# Sensor_Controller.net
KiCad netlist of a schematic drawn in Altium Designer
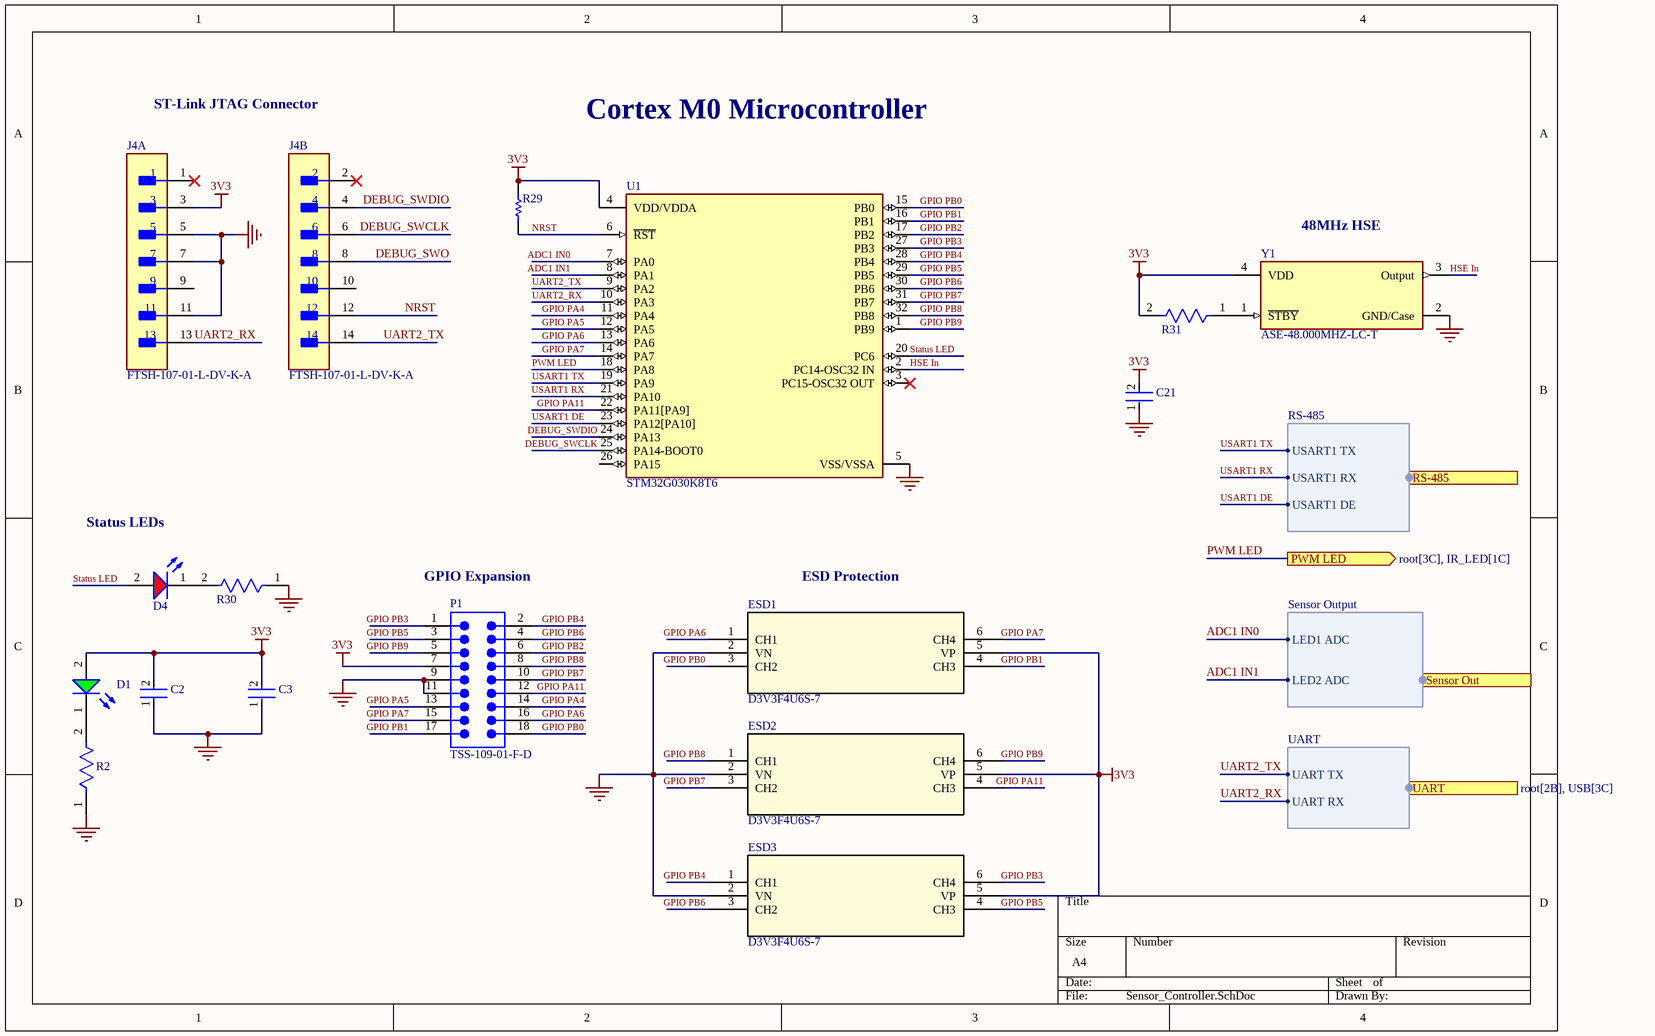
[diagram p0: Sensor_Controller.SchDoc]

(export (version "E")
  (design (tool "Eeschema 10.0.6"))
  (components
    (comp (ref "C2")
      (value "GRM188R6YA475KE15D")
      (footprint "FP-GRM188-0_2-IPC_C")
      (description "Chip Multilayer Ceramic Capacitors for General Purpose, 0603, 4.7uF, X5R, 15%, 10%, 35V")
      (fields (field (name "VOLTAGE") "35V") (field (name "TOLERANCE") "10%"))
      (libsource (lib "Altium Content Vault") (part "11868f565c42a9108669ba33697ecf6"))
    )
    (comp (ref "C3")
      (value "GRM155R71C104KA88D")
      (footprint "FP-GRM15-MFG")
      (description "CAP CER 0.1UF 16V X7R 0402")
      (fields
        (field (name "TOLERANCE") "10%")
        (field (name "OCTOPART") "https://octopart.com/grm155r71c104ka88d-murata-196880")
      )
      (libsource (lib "Altium Content Vault") (part "236180d848d6139a670b325ea6854c9"))
    )
    (comp (ref "C21")
      (value "GRM155R71C104KA88D")
      (footprint "FP-GRM15-MFG")
      (description "CAP CER 0.1UF 16V X7R 0402")
      (fields
        (field (name "TOLERANCE") "10%")
        (field (name "OCTOPART") "https://octopart.com/grm155r71c104ka88d-murata-196880")
      )
      (libsource (lib "Altium Content Vault") (part "236180d848d6139a670b325ea6854c9"))
    )
    (comp (ref "D1")
      (value "150060VS75000")
      (footprint "WL-SMCW_0603_150060xx75000")
      (description "WURTH ELEKTRONIK - 150060VS75000 - LED, Green, SMD, 0603, 30 mA, 2 V, 570 nm")
      (libsource (lib "Altium Content Vault") (part "LED_Green_2A-1K"))
    )
    (comp (ref "D4")
      (value "150060SS75000")
      (footprint "WL-SMCW_0603_150060xx75000")
      (description "Led, Red, 630 Nm, 1.9 V, 30 Ma, 60 Mcd Rohs Compliant: Yes")
      (libsource (lib "Altium Content Vault") (part "LED_Red_2A-1K"))
    )
    (comp (ref "ESD1")
      (value "D3V3F4U6S-7")
      (footprint "SOT-363_DIO")
      (description "No Description Available")
      (fields (field (name "COPYRIGHT") "Copyright (C) 2026 Ultra Librarian. All rights reserved."))
      (libsource (lib "D3V3F4U6S-7") (part "D3V3F4U6S-7"))
    )
    (comp (ref "ESD2")
      (value "D3V3F4U6S-7")
      (footprint "SOT-363_DIO")
      (description "No Description Available")
      (fields (field (name "COPYRIGHT") "Copyright (C) 2026 Ultra Librarian. All rights reserved."))
      (libsource (lib "D3V3F4U6S-7") (part "D3V3F4U6S-7"))
    )
    (comp (ref "ESD3")
      (value "D3V3F4U6S-7")
      (footprint "SOT-363_DIO")
      (description "No Description Available")
      (fields (field (name "COPYRIGHT") "Copyright (C) 2026 Ultra Librarian. All rights reserved."))
      (libsource (lib "D3V3F4U6S-7") (part "D3V3F4U6S-7"))
    )
    (comp (ref "J4")
      (value "FTSH-107-01-L-DV-K-A")
      (footprint "FP-FTSH-107-01-L-DV-K-A-MFG")
      (description "CONN HEADER SMD 14POS 1.27MM")
      (libsource (lib "Altium Content Vault") (part "45cc164b9edde9e1ad516d884ad4e1e"))
    )
    (comp (ref "P1")
      (value "TSS-109-01-F-D")
      (footprint "SMTC-TSS-109-01-X-D")
      (fields (field (name "MANUFACTURER") "Samtec"))
      (libsource (lib "Altium Content Vault") (part "SMTC-TSS-109-01-X-D"))
    )
    (comp (ref "R2")
      (value "RC0603FR-0710KL")
      (footprint "FP-RC0603-0_55-IPC_C")
      (description "RES 10K OHM 1% 1/10W 0603")
      (fields (field (name "TOLERANCE") "1%"))
      (libsource (lib "Altium Content Vault") (part "1029c3af85768c4190bb7ad29bc67b5"))
    )
    (comp (ref "R29")
      (value "TNPW040210K0DEED")
      (footprint "RESC1005X40X20NL05T10")
      (fields (field (name "MANUFACTURER") "Vishay BCcomponents"))
      (libsource (lib "Altium Content Vault") (part "RES"))
    )
    (comp (ref "R30")
      (value "RC0603FR-0710KL")
      (footprint "FP-RC0603-0_55-IPC_C")
      (description "RES 10K OHM 1% 1/10W 0603")
      (fields (field (name "TOLERANCE") "1%"))
      (libsource (lib "Altium Content Vault") (part "1029c3af85768c4190bb7ad29bc67b5"))
    )
    (comp (ref "R31")
      (value "RC0603FR-0710KL")
      (footprint "FP-RC0603-0_55-IPC_C")
      (description "RES 10K OHM 1% 1/10W 0603")
      (fields (field (name "TOLERANCE") "1%"))
      (libsource (lib "Altium Content Vault") (part "1029c3af85768c4190bb7ad29bc67b5"))
    )
    (comp (ref "U1")
      (value "STM32G030K8T6")
      (footprint "FP-LQFP32-5V-IPC_A")
      (description "IC MCU 32BIT 64KB FLASH 32LQFP")
      (libsource (lib "Altium Content Vault") (part "fea91388a178aa646681c81fcef9c35"))
    )
    (comp (ref "Y1")
      (value "ASE-48.000MHZ-LC-T")
      (footprint "FP-ASE-MFG")
      (description "XTAL Oscillator 48MHz ±50ppm CMOS 3.3V 4-SMD 3.2mm x 2.5mm")
      (libsource (lib "Altium Content Vault") (part "61a724e6190563596ac712fef61ad37"))
    )
  )
  (nets
    (net (code "5") (name "/ADC1 IN0") (class "Default")
      (node (ref "U1") (pin "7") (pinfunction "PA0_7") (pintype "bidirectional"))
    )
    (net (code "6") (name "/ADC1 IN1") (class "Default")
      (node (ref "U1") (pin "8") (pinfunction "PA1_8") (pintype "bidirectional"))
    )
    (net (code "7") (name "/DEBUG_SWCLK") (class "Default")
      (node (ref "J4") (pin "6") (pinfunction "6_6") (pintype "passive"))
      (node (ref "U1") (pin "25") (pinfunction "PA14-BOOT0_25") (pintype "bidirectional"))
    )
    (net (code "8") (name "/DEBUG_SWDIO") (class "Default")
      (node (ref "J4") (pin "4") (pinfunction "4_4") (pintype "passive"))
      (node (ref "U1") (pin "24") (pinfunction "PA13_24") (pintype "bidirectional"))
    )
    (net (code "9") (name "/DEBUG_SWO") (class "Default")
      (node (ref "J4") (pin "8") (pinfunction "8_8") (pintype "passive"))
    )
    (net (code "10") (name "/GPIO PA4") (class "Default")
      (node (ref "P1") (pin "14") (pinfunction "14_14") (pintype "passive"))
      (node (ref "U1") (pin "11") (pinfunction "PA4_11") (pintype "bidirectional"))
    )
    (net (code "11") (name "/GPIO PA5") (class "Default")
      (node (ref "P1") (pin "13") (pinfunction "13_13") (pintype "passive"))
      (node (ref "U1") (pin "12") (pinfunction "PA5_12") (pintype "bidirectional"))
    )
    (net (code "12") (name "/GPIO PA6") (class "Default")
      (node (ref "ESD1") (pin "1") (pinfunction "CH1_1") (pintype "passive"))
      (node (ref "P1") (pin "16") (pinfunction "16_16") (pintype "passive"))
      (node (ref "U1") (pin "13") (pinfunction "PA6_13") (pintype "bidirectional"))
    )
    (net (code "13") (name "/GPIO PA7") (class "Default")
      (node (ref "ESD1") (pin "6") (pinfunction "CH4_6") (pintype "passive"))
      (node (ref "P1") (pin "15") (pinfunction "15_15") (pintype "passive"))
      (node (ref "U1") (pin "14") (pinfunction "PA7_14") (pintype "bidirectional"))
    )
    (net (code "14") (name "/GPIO PA11") (class "Default")
      (node (ref "ESD2") (pin "4") (pinfunction "CH3_4") (pintype "passive"))
      (node (ref "P1") (pin "12") (pinfunction "12_12") (pintype "passive"))
      (node (ref "U1") (pin "22") (pinfunction "PA11[PA9]_22") (pintype "bidirectional"))
    )
    (net (code "15") (name "/GPIO PB0") (class "Default")
      (node (ref "ESD1") (pin "3") (pinfunction "CH2_3") (pintype "passive"))
      (node (ref "P1") (pin "18") (pinfunction "18_18") (pintype "passive"))
      (node (ref "U1") (pin "15") (pinfunction "PB0_15") (pintype "bidirectional"))
    )
    (net (code "16") (name "/GPIO PB1") (class "Default")
      (node (ref "ESD1") (pin "4") (pinfunction "CH3_4") (pintype "passive"))
      (node (ref "P1") (pin "17") (pinfunction "17_17") (pintype "passive"))
      (node (ref "U1") (pin "16") (pinfunction "PB1_16") (pintype "bidirectional"))
    )
    (net (code "17") (name "/GPIO PB2") (class "Default")
      (node (ref "P1") (pin "6") (pinfunction "6_6") (pintype "passive"))
      (node (ref "U1") (pin "17") (pinfunction "PB2_17") (pintype "bidirectional"))
    )
    (net (code "18") (name "/GPIO PB3") (class "Default")
      (node (ref "ESD3") (pin "6") (pinfunction "CH4_6") (pintype "passive"))
      (node (ref "P1") (pin "1") (pinfunction "1_1") (pintype "passive"))
      (node (ref "U1") (pin "27") (pinfunction "PB3_27") (pintype "bidirectional"))
    )
    (net (code "19") (name "/GPIO PB4") (class "Default")
      (node (ref "ESD3") (pin "1") (pinfunction "CH1_1") (pintype "passive"))
      (node (ref "P1") (pin "2") (pinfunction "2_2") (pintype "passive"))
      (node (ref "U1") (pin "28") (pinfunction "PB4_28") (pintype "bidirectional"))
    )
    (net (code "20") (name "/GPIO PB5") (class "Default")
      (node (ref "ESD3") (pin "4") (pinfunction "CH3_4") (pintype "passive"))
      (node (ref "P1") (pin "3") (pinfunction "3_3") (pintype "passive"))
      (node (ref "U1") (pin "29") (pinfunction "PB5_29") (pintype "bidirectional"))
    )
    (net (code "21") (name "/GPIO PB6") (class "Default")
      (node (ref "ESD3") (pin "3") (pinfunction "CH2_3") (pintype "passive"))
      (node (ref "P1") (pin "4") (pinfunction "4_4") (pintype "passive"))
      (node (ref "U1") (pin "30") (pinfunction "PB6_30") (pintype "bidirectional"))
    )
    (net (code "22") (name "/GPIO PB7") (class "Default")
      (node (ref "ESD2") (pin "3") (pinfunction "CH2_3") (pintype "passive"))
      (node (ref "P1") (pin "10") (pinfunction "10_10") (pintype "passive"))
      (node (ref "U1") (pin "31") (pinfunction "PB7_31") (pintype "bidirectional"))
    )
    (net (code "23") (name "/GPIO PB8") (class "Default")
      (node (ref "ESD2") (pin "1") (pinfunction "CH1_1") (pintype "passive"))
      (node (ref "P1") (pin "8") (pinfunction "8_8") (pintype "passive"))
      (node (ref "U1") (pin "32") (pinfunction "PB8_32") (pintype "bidirectional"))
    )
    (net (code "24") (name "/GPIO PB9") (class "Default")
      (node (ref "ESD2") (pin "6") (pinfunction "CH4_6") (pintype "passive"))
      (node (ref "P1") (pin "5") (pinfunction "5_5") (pintype "passive"))
      (node (ref "U1") (pin "1") (pinfunction "PB9_1") (pintype "bidirectional"))
    )
    (net (code "25") (name "/HSE In") (class "Default")
      (node (ref "U1") (pin "2") (pinfunction "PC14-OSC32_IN_2") (pintype "bidirectional"))
      (node (ref "Y1") (pin "3") (pinfunction "Output_3") (pintype "output"))
    )
    (net (code "26") (name "/NRST") (class "Default")
      (node (ref "J4") (pin "12") (pinfunction "12_12") (pintype "passive"))
      (node (ref "R29") (pin "1") (pinfunction "1_1") (pintype "passive"))
      (node (ref "U1") (pin "6") (pinfunction "~{RST}_6") (pintype "input"))
    )
    (net (code "27") (name "/PWM LED") (class "Default")
      (node (ref "U1") (pin "18") (pinfunction "PA8_18") (pintype "bidirectional"))
    )
    (net (code "28") (name "/Status LED") (class "Default")
      (node (ref "D4") (pin "2") (pinfunction "A_2") (pintype "passive"))
      (node (ref "U1") (pin "20") (pinfunction "PC6_20") (pintype "bidirectional"))
    )
    (net (code "29") (name "/UART2_RX") (class "Default")
      (node (ref "J4") (pin "13") (pinfunction "13_13") (pintype "passive"))
      (node (ref "U1") (pin "10") (pinfunction "PA3_10") (pintype "bidirectional"))
    )
    (net (code "30") (name "/UART2_TX") (class "Default")
      (node (ref "J4") (pin "14") (pinfunction "14_14") (pintype "passive"))
      (node (ref "U1") (pin "9") (pinfunction "PA2_9") (pintype "bidirectional"))
    )
    (net (code "31") (name "/USART1 DE") (class "Default")
      (node (ref "U1") (pin "23") (pinfunction "PA12[PA10]_23") (pintype "bidirectional"))
    )
    (net (code "32") (name "/USART1 RX") (class "Default")
      (node (ref "U1") (pin "21") (pinfunction "PA10_21") (pintype "bidirectional"))
    )
    (net (code "33") (name "/USART1 TX") (class "Default")
      (node (ref "U1") (pin "19") (pinfunction "PA9_19") (pintype "bidirectional"))
    )
    (net (code "37") (name "3V3") (class "Default")
      (node (ref "C2") (pin "2") (pinfunction "2_2") (pintype "passive"))
      (node (ref "C21") (pin "2") (pinfunction "2_2") (pintype "passive"))
      (node (ref "C3") (pin "2") (pinfunction "2_2") (pintype "passive"))
      (node (ref "D1") (pin "2") (pinfunction "A_2") (pintype "passive"))
      (node (ref "ESD1") (pin "5") (pinfunction "VP_5") (pintype "power_in"))
      (node (ref "ESD2") (pin "5") (pinfunction "VP_5") (pintype "power_in"))
      (node (ref "ESD3") (pin "5") (pinfunction "VP_5") (pintype "power_in"))
      (node (ref "J4") (pin "3") (pinfunction "3_3") (pintype "passive"))
      (node (ref "P1") (pin "7") (pinfunction "7_7") (pintype "passive"))
      (node (ref "R29") (pin "2") (pinfunction "2_2") (pintype "passive"))
      (node (ref "R31") (pin "2") (pinfunction "2_2") (pintype "passive"))
      (node (ref "U1") (pin "4") (pinfunction "VDD/VDDA_4") (pintype "power_in"))
      (node (ref "Y1") (pin "4") (pinfunction "VDD_4") (pintype "power_in"))
    )
    (net (code "38") (name "GND") (class "Default")
      (node (ref "C2") (pin "1") (pinfunction "1_1") (pintype "passive"))
      (node (ref "C21") (pin "1") (pinfunction "1_1") (pintype "passive"))
      (node (ref "C3") (pin "1") (pinfunction "1_1") (pintype "passive"))
      (node (ref "ESD1") (pin "2") (pinfunction "VN_2") (pintype "power_in"))
      (node (ref "ESD2") (pin "2") (pinfunction "VN_2") (pintype "power_in"))
      (node (ref "ESD3") (pin "2") (pinfunction "VN_2") (pintype "power_in"))
      (node (ref "J4") (pin "11") (pinfunction "11_11") (pintype "passive"))
      (node (ref "J4") (pin "5") (pinfunction "5_5") (pintype "passive"))
      (node (ref "J4") (pin "7") (pinfunction "7_7") (pintype "passive"))
      (node (ref "P1") (pin "11") (pinfunction "11_11") (pintype "passive"))
      (node (ref "P1") (pin "9") (pinfunction "9_9") (pintype "passive"))
      (node (ref "R2") (pin "1") (pinfunction "1_1") (pintype "passive"))
      (node (ref "R30") (pin "1") (pinfunction "1_1") (pintype "passive"))
      (node (ref "U1") (pin "5") (pinfunction "VSS/VSSA_5") (pintype "power_in"))
      (node (ref "Y1") (pin "2") (pinfunction "GND/Case_2") (pintype "power_in"))
    )
    (net (code "39") (name "Net-(D1-K)") (class "Default")
      (node (ref "D1") (pin "1") (pinfunction "K_1") (pintype "passive"))
      (node (ref "R2") (pin "2") (pinfunction "2_2") (pintype "passive"))
    )
    (net (code "40") (name "Net-(D4-K)") (class "Default")
      (node (ref "D4") (pin "1") (pinfunction "K_1") (pintype "passive"))
      (node (ref "R30") (pin "2") (pinfunction "2_2") (pintype "passive"))
    )
    (net (code "41") (name "Net-(Y1-~{STBY})") (class "Default")
      (node (ref "R31") (pin "1") (pinfunction "1_1") (pintype "passive"))
      (node (ref "Y1") (pin "1") (pinfunction "~{STBY}_1") (pintype "input"))
    )
    (net (code "42") (name "unconnected-(J4-Pad1)") (class "Default")
      (node (ref "J4") (pin "1") (pinfunction "1_1") (pintype "passive+no_connect"))
    )
    (net (code "43") (name "unconnected-(J4-Pad2)") (class "Default")
      (node (ref "J4") (pin "2") (pinfunction "2_2") (pintype "passive+no_connect"))
    )
    (net (code "44") (name "unconnected-(J4-Pad9)") (class "Default")
      (node (ref "J4") (pin "9") (pinfunction "9_9") (pintype "passive"))
    )
    (net (code "45") (name "unconnected-(J4-Pad10)") (class "Default")
      (node (ref "J4") (pin "10") (pinfunction "10_10") (pintype "passive"))
    )
    (net (code "46") (name "unconnected-(U1-PA15-Pad26)") (class "Default")
      (node (ref "U1") (pin "26") (pinfunction "PA15_26") (pintype "bidirectional"))
    )
    (net (code "47") (name "unconnected-(U1-PC15-OSC32_OUT-Pad3)") (class "Default")
      (node (ref "U1") (pin "3") (pinfunction "PC15-OSC32_OUT_3") (pintype "bidirectional+no_connect"))
    )
  )
)
